# MAX31855.net
KiCad netlist of a schematic drawn in Altium Designer
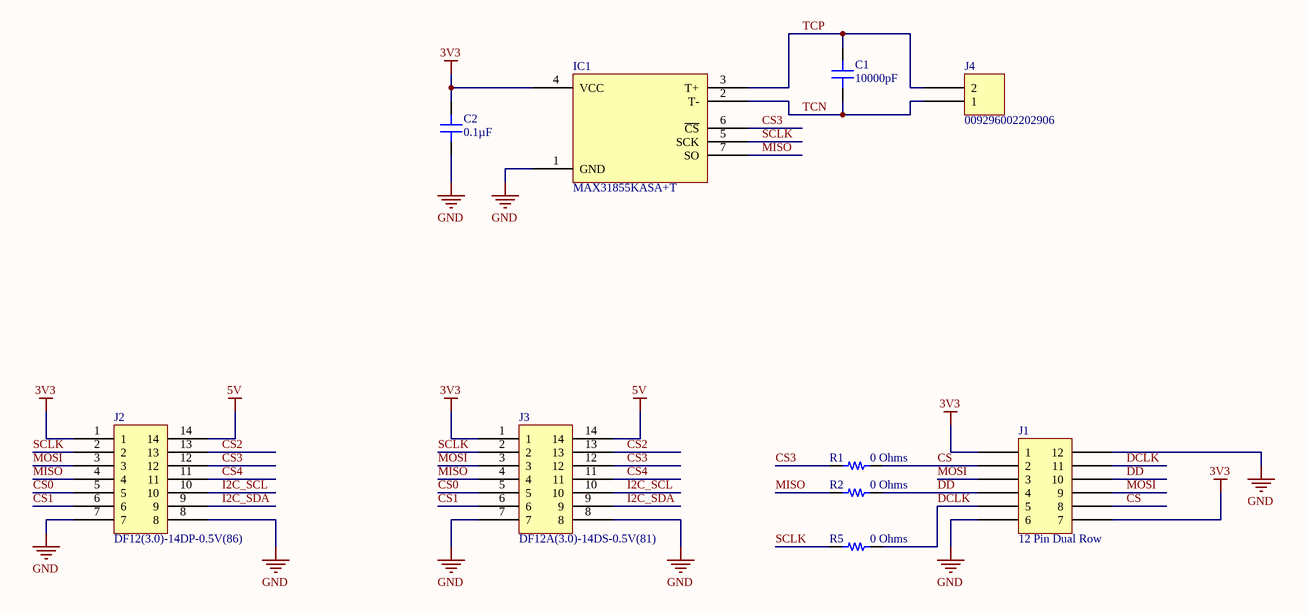
[diagram p0: MAX31855.SchDoc]

(export (version "E")
  (design (tool "Eeschema 10.0.6"))
  (components
    (comp (ref "C1")
      (value "10000pF")
      (footprint "CAP 0603_1608")
      (description "CAP CER 10000PF 100V X7R 0603")
      (fields
        (field (name "PART NUMBER") "CGA3E2X7R2A103M080AA")
        (field (name "MANUFACTURER") "TDK Corporation")
      )
      (libsource (lib "altiumlibrary.com") (part "Capacitor"))
    )
    (comp (ref "C2")
      (value "0.1µF")
      (footprint "CAP 0603_1608")
      (description "CAP CER 0.1UF 16V Y5V 0603")
      (fields (field (name "PART NUMBER") "CC0603ZRY5V7BB104") (field (name "MANUFACTURER") "Yageo"))
      (libsource (lib "altiumlibrary.com") (part "Capacitor"))
    )
    (comp (ref "IC1")
      (value "MAX31855KASA+T")
      (footprint "MAXIM SOIC-8 S8")
      (description "IC CONV THERMOCOUPLE-DGTL 8SOIC")
      (fields (field (name "MANUFACTURER") "Maxim Integrated"))
      (libsource (lib "altiumlibrary.com") (part "Maxim MAX31855"))
    )
    (comp (ref "J1")
      (value "12 Pin Dual Row")
      (footprint "TE 5650118-3 Card Edge")
      (libsource (lib "CelestialUseful") (part "12 Pin Dual Row"))
    )
    (comp (ref "J2")
      (value "DF12(3.0)-14DP-0.5V(86)")
      (footprint "HIROSE DF12 3.0-14DP-0.5V 86")
      (description "CONN HDR 14POS SMD GOLD")
      (fields (field (name "MANUFACTURER") "Hirose Electric Co Ltd"))
      (libsource (lib "altiumlibrary.com") (part "14 Pin Dual Row"))
    )
    (comp (ref "J3")
      (value "DF12A(3.0)-14DS-0.5V(81)")
      (footprint "HIROSE DF12A 3.0-14DS-0.5V 81")
      (description "CONN RCPT 14POS SMD GOLD")
      (fields (field (name "MANUFACTURER") "Hirose Electric Co Ltd"))
      (libsource (lib "altiumlibrary.com") (part "14 Pin Dual Row"))
    )
    (comp (ref "J4")
      (value "009296002202906")
      (footprint "AVX 9296002202806")
      (description "CONN WIRE POKE-IN 2POS SMD RA")
      (fields (field (name "MANUFACTURER") "AVX Corporation"))
      (libsource (lib "altiumlibrary.com") (part "2 Pin"))
    )
    (comp (ref "R1")
      (value "0 Ohms")
      (footprint "RES 0603_1608")
      (description "RES SMD 0 OHM JUMPER 1/10W 0603")
      (fields
        (field (name "PART NUMBER") "ERJ-3GEY0R00V")
        (field (name "MANUFACTURER") "Panasonic Electronic Components")
      )
      (libsource (lib "altiumlibrary.com") (part "Resistor"))
    )
    (comp (ref "R2")
      (value "0 Ohms")
      (footprint "RES 0603_1608")
      (description "RES SMD 0 OHM JUMPER 1/10W 0603")
      (fields
        (field (name "PART NUMBER") "ERJ-3GEY0R00V")
        (field (name "MANUFACTURER") "Panasonic Electronic Components")
      )
      (libsource (lib "altiumlibrary.com") (part "Resistor"))
    )
    (comp (ref "R5")
      (value "0 Ohms")
      (footprint "RES 0603_1608")
      (description "RES SMD 0 OHM JUMPER 1/10W 0603")
      (fields
        (field (name "PART NUMBER") "ERJ-3GEY0R00V")
        (field (name "MANUFACTURER") "Panasonic Electronic Components")
      )
      (libsource (lib "altiumlibrary.com") (part "Resistor"))
    )
  )
  (nets
    (net (code "1") (name "/CS") (class "Default")
      (node (ref "J1") (pin "2") (pinfunction "2_2") (pintype "passive"))
      (node (ref "J1") (pin "8") (pinfunction "8_8") (pintype "passive"))
      (node (ref "R1") (pin "2") (pinfunction "2_2") (pintype "passive"))
    )
    (net (code "2") (name "/CS0") (class "Default")
      (node (ref "J2") (pin "5") (pinfunction "5_5") (pintype "passive"))
      (node (ref "J3") (pin "5") (pinfunction "5_5") (pintype "passive"))
    )
    (net (code "3") (name "/CS1") (class "Default")
      (node (ref "J2") (pin "6") (pinfunction "6_6") (pintype "passive"))
      (node (ref "J3") (pin "6") (pinfunction "6_6") (pintype "passive"))
    )
    (net (code "4") (name "/CS2") (class "Default")
      (node (ref "J2") (pin "13") (pinfunction "13_13") (pintype "passive"))
      (node (ref "J3") (pin "13") (pinfunction "13_13") (pintype "passive"))
    )
    (net (code "5") (name "/CS3") (class "Default")
      (node (ref "IC1") (pin "6") (pinfunction "~{CS}_6") (pintype "passive"))
      (node (ref "J2") (pin "12") (pinfunction "12_12") (pintype "passive"))
      (node (ref "J3") (pin "12") (pinfunction "12_12") (pintype "passive"))
      (node (ref "R1") (pin "1") (pinfunction "1_1") (pintype "passive"))
    )
    (net (code "6") (name "/CS4") (class "Default")
      (node (ref "J2") (pin "11") (pinfunction "11_11") (pintype "passive"))
      (node (ref "J3") (pin "11") (pinfunction "11_11") (pintype "passive"))
    )
    (net (code "7") (name "/DCLK") (class "Default")
      (node (ref "J1") (pin "11") (pinfunction "11_11") (pintype "passive"))
      (node (ref "J1") (pin "5") (pinfunction "5_5") (pintype "passive"))
      (node (ref "R5") (pin "2") (pinfunction "2_2") (pintype "passive"))
    )
    (net (code "8") (name "/DD") (class "Default")
      (node (ref "J1") (pin "10") (pinfunction "10_10") (pintype "passive"))
      (node (ref "J1") (pin "4") (pinfunction "4_4") (pintype "passive"))
      (node (ref "R2") (pin "2") (pinfunction "2_2") (pintype "passive"))
    )
    (net (code "9") (name "/I2C_SCL") (class "Default")
      (node (ref "J2") (pin "10") (pinfunction "10_10") (pintype "passive"))
      (node (ref "J3") (pin "10") (pinfunction "10_10") (pintype "passive"))
    )
    (net (code "10") (name "/I2C_SDA") (class "Default")
      (node (ref "J2") (pin "9") (pinfunction "9_9") (pintype "passive"))
      (node (ref "J3") (pin "9") (pinfunction "9_9") (pintype "passive"))
    )
    (net (code "11") (name "/MISO") (class "Default")
      (node (ref "IC1") (pin "7") (pinfunction "SO_7") (pintype "passive"))
      (node (ref "J2") (pin "4") (pinfunction "4_4") (pintype "passive"))
      (node (ref "J3") (pin "4") (pinfunction "4_4") (pintype "passive"))
      (node (ref "R2") (pin "1") (pinfunction "1_1") (pintype "passive"))
    )
    (net (code "12") (name "/MOSI") (class "Default")
      (node (ref "J1") (pin "3") (pinfunction "3_3") (pintype "passive"))
      (node (ref "J1") (pin "9") (pinfunction "9_9") (pintype "passive"))
      (node (ref "J2") (pin "3") (pinfunction "3_3") (pintype "passive"))
      (node (ref "J3") (pin "3") (pinfunction "3_3") (pintype "passive"))
    )
    (net (code "13") (name "/SCLK") (class "Default")
      (node (ref "IC1") (pin "5") (pinfunction "SCK_5") (pintype "passive"))
      (node (ref "J2") (pin "2") (pinfunction "2_2") (pintype "passive"))
      (node (ref "J3") (pin "2") (pinfunction "2_2") (pintype "passive"))
      (node (ref "R5") (pin "1") (pinfunction "1_1") (pintype "passive"))
    )
    (net (code "14") (name "/TCN") (class "Default")
      (node (ref "C1") (pin "1") (pinfunction "1_1") (pintype "passive"))
      (node (ref "IC1") (pin "2") (pinfunction "T-_2") (pintype "passive"))
      (node (ref "J4") (pin "1") (pinfunction "1_1") (pintype "passive"))
    )
    (net (code "15") (name "/TCP") (class "Default")
      (node (ref "C1") (pin "2") (pinfunction "2_2") (pintype "passive"))
      (node (ref "IC1") (pin "3") (pinfunction "T+_3") (pintype "passive"))
      (node (ref "J4") (pin "2") (pinfunction "2_2") (pintype "passive"))
    )
    (net (code "16") (name "3V3") (class "Default")
      (node (ref "C2") (pin "1") (pinfunction "1_1") (pintype "passive"))
      (node (ref "IC1") (pin "4") (pinfunction "VCC_4") (pintype "passive"))
      (node (ref "J1") (pin "1") (pinfunction "1_1") (pintype "passive"))
      (node (ref "J1") (pin "7") (pinfunction "7_7") (pintype "passive"))
      (node (ref "J2") (pin "1") (pinfunction "1_1") (pintype "passive"))
      (node (ref "J3") (pin "1") (pinfunction "1_1") (pintype "passive"))
    )
    (net (code "17") (name "5V") (class "Default")
      (node (ref "J2") (pin "14") (pinfunction "14_14") (pintype "passive"))
      (node (ref "J3") (pin "14") (pinfunction "14_14") (pintype "passive"))
    )
    (net (code "18") (name "GND") (class "Default")
      (node (ref "C2") (pin "2") (pinfunction "2_2") (pintype "passive"))
      (node (ref "IC1") (pin "1") (pinfunction "GND_1") (pintype "passive"))
      (node (ref "J1") (pin "12") (pinfunction "12_12") (pintype "passive"))
      (node (ref "J1") (pin "6") (pinfunction "6_6") (pintype "passive"))
      (node (ref "J2") (pin "7") (pinfunction "7_7") (pintype "passive"))
      (node (ref "J2") (pin "8") (pinfunction "8_8") (pintype "passive"))
      (node (ref "J3") (pin "7") (pinfunction "7_7") (pintype "passive"))
      (node (ref "J3") (pin "8") (pinfunction "8_8") (pintype "passive"))
    )
  )
)
